# SCD40Breakout.net
KiCad netlist of a schematic drawn in EAGLE
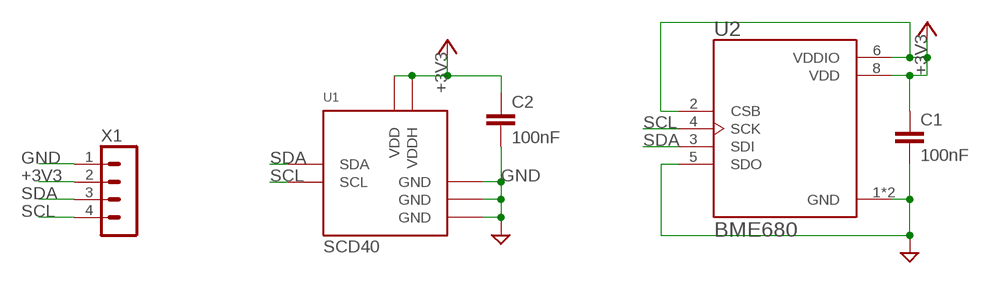
[diagram p0: schematic, sheet 1]

(export (version "E")
  (design (tool "Eeschema 10.0.6"))
  (components
    (comp (ref "C1")
      (value "100nF")
      (footprint "eagle-import:C0805")
      (libsource (lib "eagle-import") (part "C-EUC0805"))
    )
    (comp (ref "C2")
      (value "100nF")
      (footprint "eagle-import:C0805")
      (libsource (lib "eagle-import") (part "C-EUC0805"))
    )
    (comp (ref "U1")
      (value "SCD40")
      (footprint "eagle-import:SCD40")
      (libsource (lib "eagle-import") (part "SCD40"))
    )
    (comp (ref "U2")
      (value "BME680")
      (footprint "eagle-import:PSON80P300X300X100-8N")
      (fields (field (name "MF") "Bosch Sensortec"))
      (libsource (lib "eagle-import") (part "BME680"))
    )
    (comp (ref "X1")
      (value "B4B-PH-K")
      (footprint "eagle-import:B4B-PH-K")
      (libsource (lib "eagle-import") (part "B4B-PH-K"))
    )
  )
  (nets
    (net (code "1") (name "+3V3") (class "Default")
      (node (ref "C1") (pin "1") (pinfunction "1_1") (pintype "passive"))
      (node (ref "C2") (pin "1") (pinfunction "1_1") (pintype "passive"))
      (node (ref "U1") (pin "P$19") (pinfunction "VDDH_P$19") (pintype "power_in"))
      (node (ref "U1") (pin "P$7") (pinfunction "VDD_P$7") (pintype "power_in"))
      (node (ref "U2") (pin "2") (pinfunction "CSB_2") (pintype "input"))
      (node (ref "U2") (pin "6") (pinfunction "VDDIO_6") (pintype "power_in"))
      (node (ref "U2") (pin "8") (pinfunction "VDD_8") (pintype "power_in"))
      (node (ref "X1") (pin "2") (pinfunction "2_2") (pintype "passive"))
    )
    (net (code "2") (name "/SCL") (class "Default")
      (node (ref "U1") (pin "P$9") (pinfunction "SCL_P$9") (pintype "bidirectional"))
      (node (ref "U2") (pin "4") (pinfunction "SCK_4") (pintype "input"))
      (node (ref "X1") (pin "4") (pinfunction "4_4") (pintype "passive"))
    )
    (net (code "3") (name "/SDA") (class "Default")
      (node (ref "U1") (pin "P$10") (pinfunction "SDA_P$10") (pintype "bidirectional"))
      (node (ref "U2") (pin "3") (pinfunction "SDI_3") (pintype "bidirectional"))
      (node (ref "X1") (pin "3") (pinfunction "3_3") (pintype "passive"))
    )
    (net (code "4") (name "GND") (class "Default")
      (node (ref "C1") (pin "2") (pinfunction "2_2") (pintype "passive"))
      (node (ref "C2") (pin "2") (pinfunction "2_2") (pintype "passive"))
      (node (ref "U1") (pin "P$20") (pinfunction "GND_P$20") (pintype "power_in"))
      (node (ref "U1") (pin "P$21") (pinfunction "GND_P$21") (pintype "power_in"))
      (node (ref "U1") (pin "P$6") (pinfunction "GND_P$6") (pintype "power_in"))
      (node (ref "U2") (pin "1") (pinfunction "GND_1") (pintype "power_in"))
      (node (ref "U2") (pin "5") (pinfunction "SDO_5") (pintype "bidirectional"))
      (node (ref "U2") (pin "7") (pinfunction "GND_7") (pintype "power_in"))
      (node (ref "X1") (pin "1") (pinfunction "1_1") (pintype "passive"))
    )
  )
)
